# Power_Input.net
KiCad netlist of a schematic drawn in Altium Designer
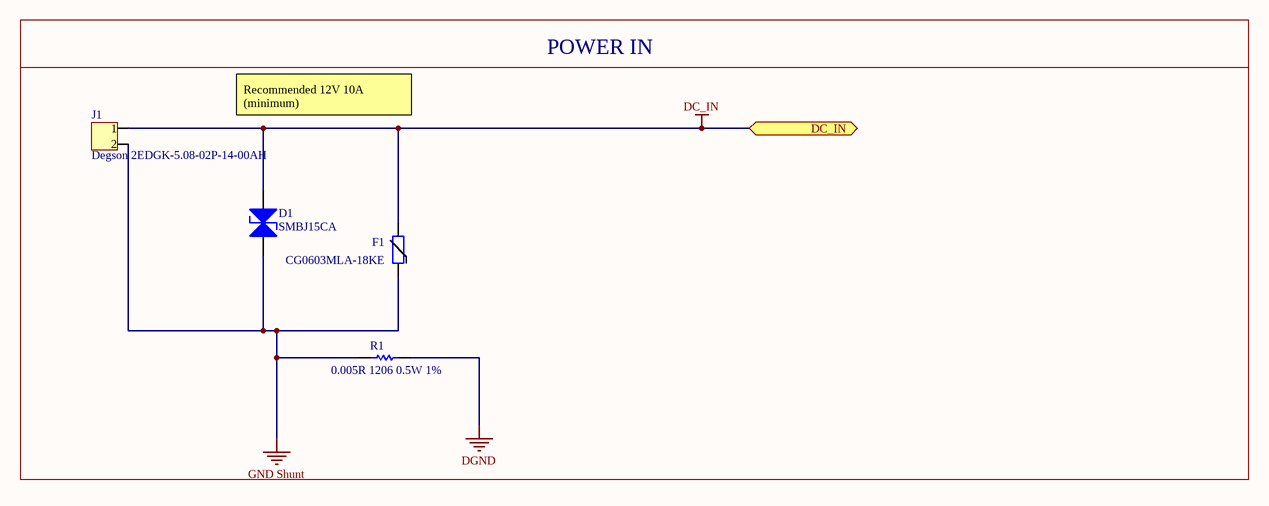
[diagram p0: Power_Input.SchDoc]

(export (version "E")
  (design (tool "Eeschema 10.0.6"))
  (components
    (comp (ref "D1")
      (value "SMBJ15CA")
      (footprint "PCB-acsqsz06h0bi34fqghyj-1")
      (description "SMBJ15 Series 24.4 V 600 W Bi-Directional Transient Voltage Suppressor-DO-214AA")
      (libsource (lib "CommunityVault") (part "SYM-f09b39914f642f5c-1"))
    )
    (comp (ref "F1")
      (value "CG0603MLA-18KE")
      (footprint "CAPC1608X60X35NL10T15")
      (description "Var MOV 14VAC 18VDC 30A 24.2V 0603 SMD Paper T/R Var MOV 14VAC 18VDC 30A 24.2V 0603 SMD Paper T/R")
      (libsource (lib "FavoritesLibrary") (part "SYM-234feae503b6fc88-1"))
    )
    (comp (ref "J1")
      (value "Degson 2EDGK-5.08-02P-14-00AH")
      (footprint "PCB-h4cyb3wxd4gf7j132tzl-1")
      (description "Terminal block, 5mm 2 Pos, through hole male.")
      (fields (field (name "MANUFACTURER PART NUMBER") "2EDGK-5.08-02P-14-00AH + 2EDGVC-5.08-02P"))
      (libsource (lib "CommunityVault") (part "CMP-7a42b7ee166ba585-1"))
    )
    (comp (ref "R1")
      (value "0.005R 1206 0.5W 1%")
      (footprint "CAPC3216X180X55ML20T25")
      (fields (field (name "MANUFACTURER PART NUMBER") "WSLP12065L000FEA") (field (name "POWER") "1W"))
      (libsource (lib "CommunityVault") (part "CMP-0abdc173b10ad57a-1"))
    )
  )
  (nets
    (net (code "1") (name "DC_IN") (class "Default")
      (node (ref "D1") (pin "2") (pinfunction "K_2") (pintype "passive"))
      (node (ref "F1") (pin "2") (pinfunction "2_2") (pintype "passive"))
      (node (ref "J1") (pin "1") (pinfunction "1_1") (pintype "passive"))
    )
    (net (code "2") (name "DGND") (class "Default")
      (node (ref "R1") (pin "1") (pinfunction "1_1") (pintype "passive"))
    )
    (net (code "3") (name "GND Shunt") (class "Default")
      (node (ref "D1") (pin "1") (pinfunction "A_1") (pintype "passive"))
      (node (ref "F1") (pin "1") (pinfunction "1_1") (pintype "passive"))
      (node (ref "J1") (pin "2") (pinfunction "2_2") (pintype "passive"))
      (node (ref "R1") (pin "2") (pinfunction "2_2") (pintype "passive"))
    )
  )
)
